# EEM_Connectors.net
KiCad netlist of a schematic drawn in Altium Designer
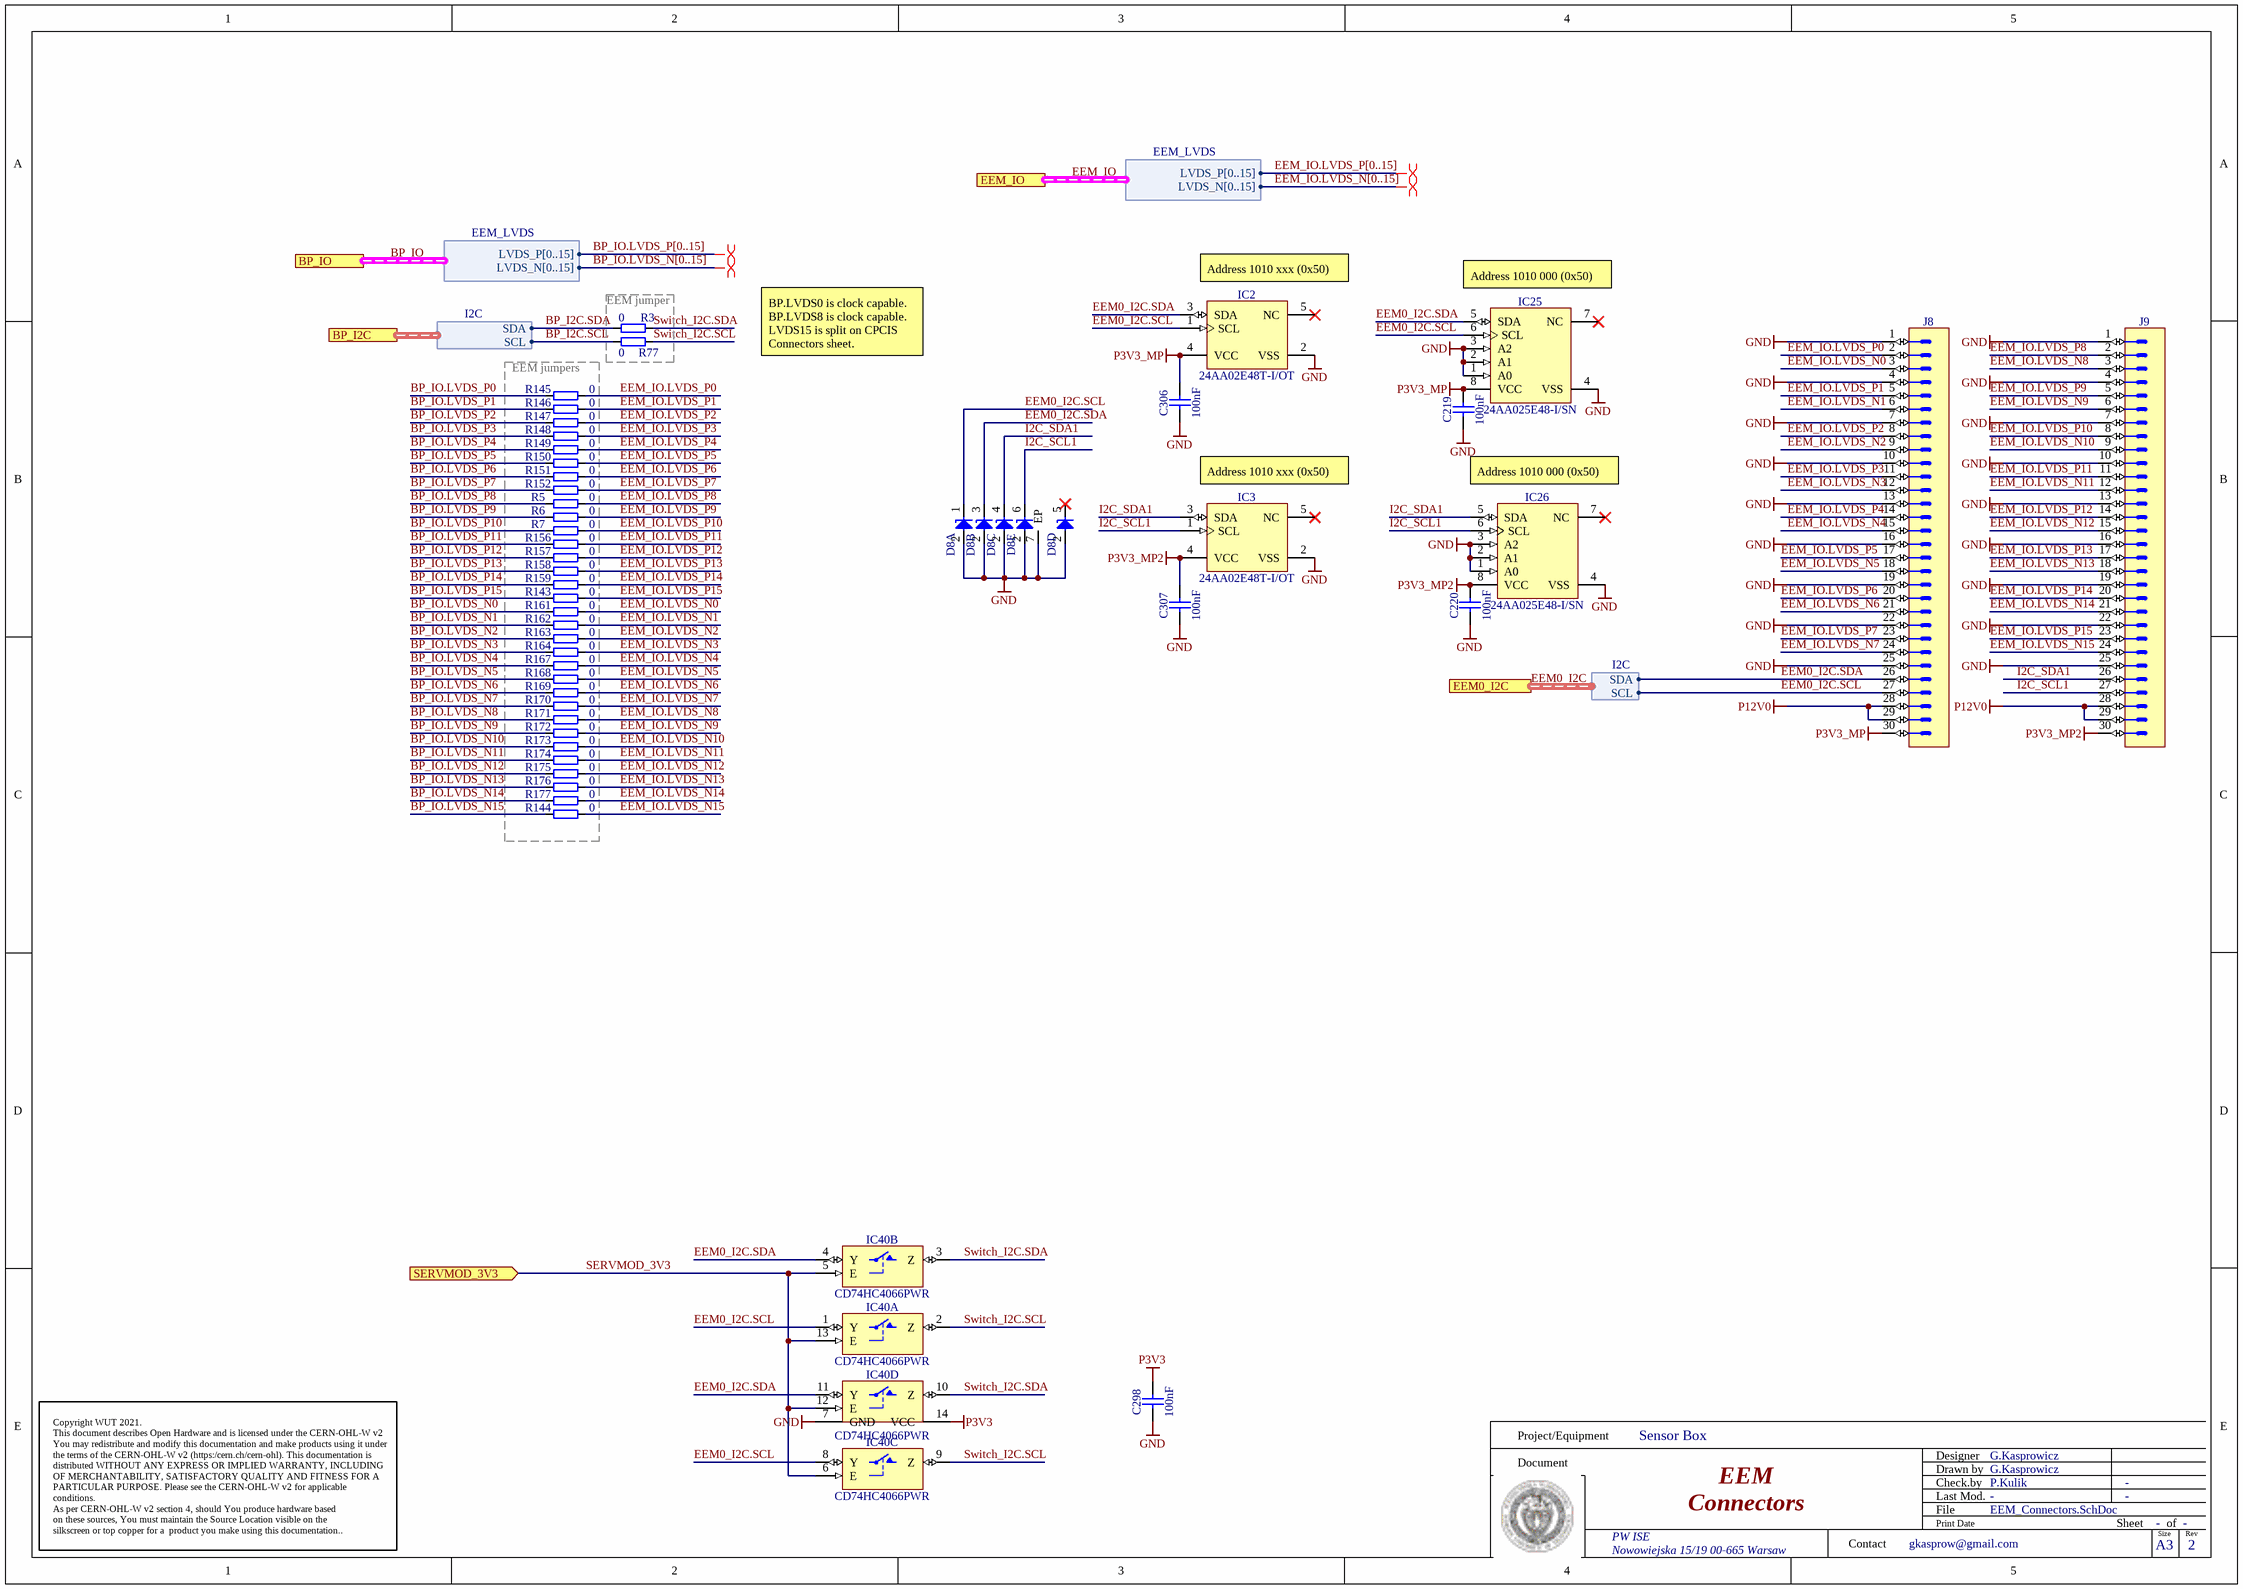
[diagram p0: EEM_Connectors.SchDoc]

(export (version "E")
  (design (tool "Eeschema 10.0.6"))
  (components
    (comp (ref "C219")
      (value "100nF")
      (footprint "CAPC1005X55N")
      (description "Non-polarised capacitor")
      (fields
        (field (name "PART NUMBER") "CC0402_100NF_50V_10%_X7R")
        (field (name "VOLTAGE") "50V")
        (field (name "AUTHOR") "CERN DEM MR")
      )
      (libsource (lib "Capacitors") (part "Capacitor - non polarized"))
    )
    (comp (ref "C220")
      (value "100nF")
      (footprint "CAPC1005X55N")
      (description "Non-polarised capacitor")
      (fields
        (field (name "PART NUMBER") "CC0402_100NF_50V_10%_X7R")
        (field (name "VOLTAGE") "50V")
        (field (name "AUTHOR") "CERN DEM MR")
      )
      (libsource (lib "Capacitors") (part "Capacitor - non polarized"))
    )
    (comp (ref "C298")
      (value "100nF")
      (footprint "CAPC1005X55N")
      (description "Non-polarised capacitor")
      (fields
        (field (name "PART NUMBER") "CC0402_100NF_50V_10%_X7R")
        (field (name "VOLTAGE") "50V")
        (field (name "AUTHOR") "CERN DEM MR")
      )
      (libsource (lib "Capacitors") (part "Capacitor - non polarized"))
    )
    (comp (ref "C306")
      (value "100nF")
      (footprint "CAPC1005X55N")
      (description "Non-polarised capacitor")
      (fields
        (field (name "PART NUMBER") "CC0402_100NF_50V_10%_X7R")
        (field (name "VOLTAGE") "50V")
        (field (name "AUTHOR") "CERN DEM MR")
      )
      (libsource (lib "Capacitors") (part "Capacitor - non polarized"))
    )
    (comp (ref "C307")
      (value "100nF")
      (footprint "CAPC1005X55N")
      (description "Non-polarised capacitor")
      (fields
        (field (name "PART NUMBER") "CC0402_100NF_50V_10%_X7R")
        (field (name "VOLTAGE") "50V")
        (field (name "AUTHOR") "CERN DEM MR")
      )
      (libsource (lib "Capacitors") (part "Capacitor - non polarized"))
    )
    (comp (ref "D8")
      (value "UCLAMP3305P.TCT")
      (footprint "SON50P160X65_HS-7N")
      (description "Diode TVS Quint Common Anode Uni-Dir 3.3V 40W 6-Pin SLP EP T/R")
      (libsource (lib "TechnoSystem Workspace") (part "D-AK-2"))
    )
    (comp (ref "IC2")
      (value "24AA02E48T-I/OT")
      (footprint "SOT95P280X145-5N")
      (description "1.7V-5.5V, 2K I2C Serial EEPROM With EUI-48 Node Identity")
      (fields (field (name "MANUFACTURER") "MICROCHIP TECHNOLOGY") (field (name "AUTHOR") "CERN DEM MR"))
      (libsource (lib "ICs And Semiconductors") (part "24AA02E48T-I/OT"))
    )
    (comp (ref "IC3")
      (value "24AA02E48T-I/OT")
      (footprint "SOT95P280X145-5N")
      (description "1.7V-5.5V, 2K I2C Serial EEPROM With EUI-48 Node Identity")
      (fields (field (name "MANUFACTURER") "MICROCHIP TECHNOLOGY") (field (name "AUTHOR") "CERN DEM MR"))
      (libsource (lib "ICs And Semiconductors") (part "24AA02E48T-I/OT"))
    )
    (comp (ref "IC25")
      (value "24AA025E48-I/SN")
      (footprint "SOIC127P600X175-8N")
      (description "1.7V-5.5V, 2K I2C™ Serial EEPROMs with EUI-48™ Node Identity")
      (fields (field (name "MANUFACTURER") "MICROCHIP TECHNOLOGY") (field (name "AUTHOR") "CERN DEM MR"))
      (libsource (lib "ICs And Semiconductors") (part "24AA025E48-I/SN"))
    )
    (comp (ref "IC26")
      (value "24AA025E48-I/SN")
      (footprint "SOIC127P600X175-8N")
      (description "1.7V-5.5V, 2K I2C™ Serial EEPROMs with EUI-48™ Node Identity")
      (fields (field (name "MANUFACTURER") "MICROCHIP TECHNOLOGY") (field (name "AUTHOR") "CERN DEM MR"))
      (libsource (lib "ICs And Semiconductors") (part "24AA025E48-I/SN"))
    )
    (comp (ref "IC40")
      (value "CD74HC4066PWR")
      (footprint "CD74HC4066PWR")
      (description "12-V, 1: 1 (SPST), (SPST), 4-channel analog switch 14-TSSOP -55 to 125")
      (libsource (lib "TechnoSystem Workspace") (part "CD74HC4066PWR-Symbol-1"))
    )
    (comp (ref "J8")
      (value "~")
      (footprint "3M_N2530-6002RB")
      (description "Connector 30 Male")
      (fields
        (field (name "PART NUMBER") "3M_N2530-6002RB")
        (field (name "MANUFACTURER") "3M")
        (field (name "AUTHOR") "CERN DEM JLC")
      )
      (libsource (lib "Connectors") (part "Connector 30 Male"))
    )
    (comp (ref "J9")
      (value "~")
      (footprint "3M_N2530-6002RB")
      (description "Connector 30 Male")
      (fields
        (field (name "PART NUMBER") "3M_N2530-6002RB")
        (field (name "MANUFACTURER") "3M")
        (field (name "AUTHOR") "CERN DEM JLC")
      )
      (libsource (lib "Connectors") (part "Connector 30 Male"))
    )
    (comp (ref "R3")
      (value "0")
      (footprint "RESC1005X40N")
      (description "Resistor")
      (fields
        (field (name "PART NUMBER") "R0402_0R_JUMPER")
        (field (name "MANUFACTURER") "GENERIC")
        (field (name "AUTHOR") "CERN DEM JLC")
      )
      (libsource (lib "Resistors") (part "Resistor"))
    )
    (comp (ref "R5")
      (value "0")
      (footprint "RESC1005X40N")
      (description "Resistor")
      (fields
        (field (name "PART NUMBER") "R0402_0R_JUMPER")
        (field (name "MANUFACTURER") "GENERIC")
        (field (name "AUTHOR") "CERN DEM JLC")
      )
      (libsource (lib "Resistors") (part "Resistor"))
    )
    (comp (ref "R6")
      (value "0")
      (footprint "RESC1005X40N")
      (description "Resistor")
      (fields
        (field (name "PART NUMBER") "R0402_0R_JUMPER")
        (field (name "MANUFACTURER") "GENERIC")
        (field (name "AUTHOR") "CERN DEM JLC")
      )
      (libsource (lib "Resistors") (part "Resistor"))
    )
    (comp (ref "R7")
      (value "0")
      (footprint "RESC1005X40N")
      (description "Resistor")
      (fields
        (field (name "PART NUMBER") "R0402_0R_JUMPER")
        (field (name "MANUFACTURER") "GENERIC")
        (field (name "AUTHOR") "CERN DEM JLC")
      )
      (libsource (lib "Resistors") (part "Resistor"))
    )
    (comp (ref "R77")
      (value "0")
      (footprint "RESC1005X40N")
      (description "Resistor")
      (fields
        (field (name "PART NUMBER") "R0402_0R_JUMPER")
        (field (name "MANUFACTURER") "GENERIC")
        (field (name "AUTHOR") "CERN DEM JLC")
      )
      (libsource (lib "Resistors") (part "Resistor"))
    )
    (comp (ref "R143")
      (value "0")
      (footprint "RESC1005X40N")
      (description "Resistor")
      (fields
        (field (name "PART NUMBER") "R0402_0R_JUMPER")
        (field (name "MANUFACTURER") "GENERIC")
        (field (name "AUTHOR") "CERN DEM JLC")
      )
      (libsource (lib "Resistors") (part "Resistor"))
    )
    (comp (ref "R144")
      (value "0")
      (footprint "RESC1005X40N")
      (description "Resistor")
      (fields
        (field (name "PART NUMBER") "R0402_0R_JUMPER")
        (field (name "MANUFACTURER") "GENERIC")
        (field (name "AUTHOR") "CERN DEM JLC")
      )
      (libsource (lib "Resistors") (part "Resistor"))
    )
    (comp (ref "R145")
      (value "0")
      (footprint "RESC1005X40N")
      (description "Resistor")
      (fields
        (field (name "PART NUMBER") "R0402_0R_JUMPER")
        (field (name "MANUFACTURER") "GENERIC")
        (field (name "AUTHOR") "CERN DEM JLC")
      )
      (libsource (lib "Resistors") (part "Resistor"))
    )
    (comp (ref "R146")
      (value "0")
      (footprint "RESC1005X40N")
      (description "Resistor")
      (fields
        (field (name "PART NUMBER") "R0402_0R_JUMPER")
        (field (name "MANUFACTURER") "GENERIC")
        (field (name "AUTHOR") "CERN DEM JLC")
      )
      (libsource (lib "Resistors") (part "Resistor"))
    )
    (comp (ref "R147")
      (value "0")
      (footprint "RESC1005X40N")
      (description "Resistor")
      (fields
        (field (name "PART NUMBER") "R0402_0R_JUMPER")
        (field (name "MANUFACTURER") "GENERIC")
        (field (name "AUTHOR") "CERN DEM JLC")
      )
      (libsource (lib "Resistors") (part "Resistor"))
    )
    (comp (ref "R148")
      (value "0")
      (footprint "RESC1005X40N")
      (description "Resistor")
      (fields
        (field (name "PART NUMBER") "R0402_0R_JUMPER")
        (field (name "MANUFACTURER") "GENERIC")
        (field (name "AUTHOR") "CERN DEM JLC")
      )
      (libsource (lib "Resistors") (part "Resistor"))
    )
    (comp (ref "R149")
      (value "0")
      (footprint "RESC1005X40N")
      (description "Resistor")
      (fields
        (field (name "PART NUMBER") "R0402_0R_JUMPER")
        (field (name "MANUFACTURER") "GENERIC")
        (field (name "AUTHOR") "CERN DEM JLC")
      )
      (libsource (lib "Resistors") (part "Resistor"))
    )
    (comp (ref "R150")
      (value "0")
      (footprint "RESC1005X40N")
      (description "Resistor")
      (fields
        (field (name "PART NUMBER") "R0402_0R_JUMPER")
        (field (name "MANUFACTURER") "GENERIC")
        (field (name "AUTHOR") "CERN DEM JLC")
      )
      (libsource (lib "Resistors") (part "Resistor"))
    )
    (comp (ref "R151")
      (value "0")
      (footprint "RESC1005X40N")
      (description "Resistor")
      (fields
        (field (name "PART NUMBER") "R0402_0R_JUMPER")
        (field (name "MANUFACTURER") "GENERIC")
        (field (name "AUTHOR") "CERN DEM JLC")
      )
      (libsource (lib "Resistors") (part "Resistor"))
    )
    (comp (ref "R152")
      (value "0")
      (footprint "RESC1005X40N")
      (description "Resistor")
      (fields
        (field (name "PART NUMBER") "R0402_0R_JUMPER")
        (field (name "MANUFACTURER") "GENERIC")
        (field (name "AUTHOR") "CERN DEM JLC")
      )
      (libsource (lib "Resistors") (part "Resistor"))
    )
    (comp (ref "R156")
      (value "0")
      (footprint "RESC1005X40N")
      (description "Resistor")
      (fields
        (field (name "PART NUMBER") "R0402_0R_JUMPER")
        (field (name "MANUFACTURER") "GENERIC")
        (field (name "AUTHOR") "CERN DEM JLC")
      )
      (libsource (lib "Resistors") (part "Resistor"))
    )
    (comp (ref "R157")
      (value "0")
      (footprint "RESC1005X40N")
      (description "Resistor")
      (fields
        (field (name "PART NUMBER") "R0402_0R_JUMPER")
        (field (name "MANUFACTURER") "GENERIC")
        (field (name "AUTHOR") "CERN DEM JLC")
      )
      (libsource (lib "Resistors") (part "Resistor"))
    )
    (comp (ref "R158")
      (value "0")
      (footprint "RESC1005X40N")
      (description "Resistor")
      (fields
        (field (name "PART NUMBER") "R0402_0R_JUMPER")
        (field (name "MANUFACTURER") "GENERIC")
        (field (name "AUTHOR") "CERN DEM JLC")
      )
      (libsource (lib "Resistors") (part "Resistor"))
    )
    (comp (ref "R159")
      (value "0")
      (footprint "RESC1005X40N")
      (description "Resistor")
      (fields
        (field (name "PART NUMBER") "R0402_0R_JUMPER")
        (field (name "MANUFACTURER") "GENERIC")
        (field (name "AUTHOR") "CERN DEM JLC")
      )
      (libsource (lib "Resistors") (part "Resistor"))
    )
    (comp (ref "R161")
      (value "0")
      (footprint "RESC1005X40N")
      (description "Resistor")
      (fields
        (field (name "PART NUMBER") "R0402_0R_JUMPER")
        (field (name "MANUFACTURER") "GENERIC")
        (field (name "AUTHOR") "CERN DEM JLC")
      )
      (libsource (lib "Resistors") (part "Resistor"))
    )
    (comp (ref "R162")
      (value "0")
      (footprint "RESC1005X40N")
      (description "Resistor")
      (fields
        (field (name "PART NUMBER") "R0402_0R_JUMPER")
        (field (name "MANUFACTURER") "GENERIC")
        (field (name "AUTHOR") "CERN DEM JLC")
      )
      (libsource (lib "Resistors") (part "Resistor"))
    )
    (comp (ref "R163")
      (value "0")
      (footprint "RESC1005X40N")
      (description "Resistor")
      (fields
        (field (name "PART NUMBER") "R0402_0R_JUMPER")
        (field (name "MANUFACTURER") "GENERIC")
        (field (name "AUTHOR") "CERN DEM JLC")
      )
      (libsource (lib "Resistors") (part "Resistor"))
    )
    (comp (ref "R164")
      (value "0")
      (footprint "RESC1005X40N")
      (description "Resistor")
      (fields
        (field (name "PART NUMBER") "R0402_0R_JUMPER")
        (field (name "MANUFACTURER") "GENERIC")
        (field (name "AUTHOR") "CERN DEM JLC")
      )
      (libsource (lib "Resistors") (part "Resistor"))
    )
    (comp (ref "R167")
      (value "0")
      (footprint "RESC1005X40N")
      (description "Resistor")
      (fields
        (field (name "PART NUMBER") "R0402_0R_JUMPER")
        (field (name "MANUFACTURER") "GENERIC")
        (field (name "AUTHOR") "CERN DEM JLC")
      )
      (libsource (lib "Resistors") (part "Resistor"))
    )
    (comp (ref "R168")
      (value "0")
      (footprint "RESC1005X40N")
      (description "Resistor")
      (fields
        (field (name "PART NUMBER") "R0402_0R_JUMPER")
        (field (name "MANUFACTURER") "GENERIC")
        (field (name "AUTHOR") "CERN DEM JLC")
      )
      (libsource (lib "Resistors") (part "Resistor"))
    )
    (comp (ref "R169")
      (value "0")
      (footprint "RESC1005X40N")
      (description "Resistor")
      (fields
        (field (name "PART NUMBER") "R0402_0R_JUMPER")
        (field (name "MANUFACTURER") "GENERIC")
        (field (name "AUTHOR") "CERN DEM JLC")
      )
      (libsource (lib "Resistors") (part "Resistor"))
    )
    (comp (ref "R170")
      (value "0")
      (footprint "RESC1005X40N")
      (description "Resistor")
      (fields
        (field (name "PART NUMBER") "R0402_0R_JUMPER")
        (field (name "MANUFACTURER") "GENERIC")
        (field (name "AUTHOR") "CERN DEM JLC")
      )
      (libsource (lib "Resistors") (part "Resistor"))
    )
    (comp (ref "R171")
      (value "0")
      (footprint "RESC1005X40N")
      (description "Resistor")
      (fields
        (field (name "PART NUMBER") "R0402_0R_JUMPER")
        (field (name "MANUFACTURER") "GENERIC")
        (field (name "AUTHOR") "CERN DEM JLC")
      )
      (libsource (lib "Resistors") (part "Resistor"))
    )
    (comp (ref "R172")
      (value "0")
      (footprint "RESC1005X40N")
      (description "Resistor")
      (fields
        (field (name "PART NUMBER") "R0402_0R_JUMPER")
        (field (name "MANUFACTURER") "GENERIC")
        (field (name "AUTHOR") "CERN DEM JLC")
      )
      (libsource (lib "Resistors") (part "Resistor"))
    )
    (comp (ref "R173")
      (value "0")
      (footprint "RESC1005X40N")
      (description "Resistor")
      (fields
        (field (name "PART NUMBER") "R0402_0R_JUMPER")
        (field (name "MANUFACTURER") "GENERIC")
        (field (name "AUTHOR") "CERN DEM JLC")
      )
      (libsource (lib "Resistors") (part "Resistor"))
    )
    (comp (ref "R174")
      (value "0")
      (footprint "RESC1005X40N")
      (description "Resistor")
      (fields
        (field (name "PART NUMBER") "R0402_0R_JUMPER")
        (field (name "MANUFACTURER") "GENERIC")
        (field (name "AUTHOR") "CERN DEM JLC")
      )
      (libsource (lib "Resistors") (part "Resistor"))
    )
    (comp (ref "R175")
      (value "0")
      (footprint "RESC1005X40N")
      (description "Resistor")
      (fields
        (field (name "PART NUMBER") "R0402_0R_JUMPER")
        (field (name "MANUFACTURER") "GENERIC")
        (field (name "AUTHOR") "CERN DEM JLC")
      )
      (libsource (lib "Resistors") (part "Resistor"))
    )
    (comp (ref "R176")
      (value "0")
      (footprint "RESC1005X40N")
      (description "Resistor")
      (fields
        (field (name "PART NUMBER") "R0402_0R_JUMPER")
        (field (name "MANUFACTURER") "GENERIC")
        (field (name "AUTHOR") "CERN DEM JLC")
      )
      (libsource (lib "Resistors") (part "Resistor"))
    )
    (comp (ref "R177")
      (value "0")
      (footprint "RESC1005X40N")
      (description "Resistor")
      (fields
        (field (name "PART NUMBER") "R0402_0R_JUMPER")
        (field (name "MANUFACTURER") "GENERIC")
        (field (name "AUTHOR") "CERN DEM JLC")
      )
      (libsource (lib "Resistors") (part "Resistor"))
    )
  )
  (nets
    (net (code "5") (name "/BP_I2C.SCL") (class "Default")
      (node (ref "R77") (pin "1") (pinfunction "1_1") (pintype "passive"))
    )
    (net (code "6") (name "/BP_I2C.SDA") (class "Default")
      (node (ref "R3") (pin "1") (pinfunction "1_1") (pintype "passive"))
    )
    (net (code "7") (name "/BP_IO.LVDS_N0") (class "Default")
      (node (ref "R161") (pin "1") (pinfunction "1_1") (pintype "passive"))
    )
    (net (code "8") (name "/BP_IO.LVDS_N1") (class "Default")
      (node (ref "R162") (pin "1") (pinfunction "1_1") (pintype "passive"))
    )
    (net (code "9") (name "/BP_IO.LVDS_N2") (class "Default")
      (node (ref "R163") (pin "1") (pinfunction "1_1") (pintype "passive"))
    )
    (net (code "10") (name "/BP_IO.LVDS_N3") (class "Default")
      (node (ref "R164") (pin "1") (pinfunction "1_1") (pintype "passive"))
    )
    (net (code "11") (name "/BP_IO.LVDS_N4") (class "Default")
      (node (ref "R167") (pin "1") (pinfunction "1_1") (pintype "passive"))
    )
    (net (code "12") (name "/BP_IO.LVDS_N5") (class "Default")
      (node (ref "R168") (pin "1") (pinfunction "1_1") (pintype "passive"))
    )
    (net (code "13") (name "/BP_IO.LVDS_N6") (class "Default")
      (node (ref "R169") (pin "1") (pinfunction "1_1") (pintype "passive"))
    )
    (net (code "14") (name "/BP_IO.LVDS_N7") (class "Default")
      (node (ref "R170") (pin "1") (pinfunction "1_1") (pintype "passive"))
    )
    (net (code "15") (name "/BP_IO.LVDS_N8") (class "Default")
      (node (ref "R171") (pin "1") (pinfunction "1_1") (pintype "passive"))
    )
    (net (code "16") (name "/BP_IO.LVDS_N9") (class "Default")
      (node (ref "R172") (pin "1") (pinfunction "1_1") (pintype "passive"))
    )
    (net (code "17") (name "/BP_IO.LVDS_N10") (class "Default")
      (node (ref "R173") (pin "1") (pinfunction "1_1") (pintype "passive"))
    )
    (net (code "18") (name "/BP_IO.LVDS_N11") (class "Default")
      (node (ref "R174") (pin "1") (pinfunction "1_1") (pintype "passive"))
    )
    (net (code "19") (name "/BP_IO.LVDS_N12") (class "Default")
      (node (ref "R175") (pin "1") (pinfunction "1_1") (pintype "passive"))
    )
    (net (code "20") (name "/BP_IO.LVDS_N13") (class "Default")
      (node (ref "R176") (pin "1") (pinfunction "1_1") (pintype "passive"))
    )
    (net (code "21") (name "/BP_IO.LVDS_N14") (class "Default")
      (node (ref "R177") (pin "1") (pinfunction "1_1") (pintype "passive"))
    )
    (net (code "22") (name "/BP_IO.LVDS_N15") (class "Default")
      (node (ref "R144") (pin "2") (pinfunction "2_2") (pintype "passive"))
    )
    (net (code "23") (name "/BP_IO.LVDS_P0") (class "Default")
      (node (ref "R145") (pin "1") (pinfunction "1_1") (pintype "passive"))
    )
    (net (code "24") (name "/BP_IO.LVDS_P1") (class "Default")
      (node (ref "R146") (pin "1") (pinfunction "1_1") (pintype "passive"))
    )
    (net (code "25") (name "/BP_IO.LVDS_P2") (class "Default")
      (node (ref "R147") (pin "1") (pinfunction "1_1") (pintype "passive"))
    )
    (net (code "26") (name "/BP_IO.LVDS_P3") (class "Default")
      (node (ref "R148") (pin "1") (pinfunction "1_1") (pintype "passive"))
    )
    (net (code "27") (name "/BP_IO.LVDS_P4") (class "Default")
      (node (ref "R149") (pin "1") (pinfunction "1_1") (pintype "passive"))
    )
    (net (code "28") (name "/BP_IO.LVDS_P5") (class "Default")
      (node (ref "R150") (pin "1") (pinfunction "1_1") (pintype "passive"))
    )
    (net (code "29") (name "/BP_IO.LVDS_P6") (class "Default")
      (node (ref "R151") (pin "1") (pinfunction "1_1") (pintype "passive"))
    )
    (net (code "30") (name "/BP_IO.LVDS_P7") (class "Default")
      (node (ref "R152") (pin "1") (pinfunction "1_1") (pintype "passive"))
    )
    (net (code "31") (name "/BP_IO.LVDS_P8") (class "Default")
      (node (ref "R5") (pin "1") (pinfunction "1_1") (pintype "passive"))
    )
    (net (code "32") (name "/BP_IO.LVDS_P9") (class "Default")
      (node (ref "R6") (pin "1") (pinfunction "1_1") (pintype "passive"))
    )
    (net (code "33") (name "/BP_IO.LVDS_P10") (class "Default")
      (node (ref "R7") (pin "1") (pinfunction "1_1") (pintype "passive"))
    )
    (net (code "34") (name "/BP_IO.LVDS_P11") (class "Default")
      (node (ref "R156") (pin "1") (pinfunction "1_1") (pintype "passive"))
    )
    (net (code "35") (name "/BP_IO.LVDS_P12") (class "Default")
      (node (ref "R157") (pin "1") (pinfunction "1_1") (pintype "passive"))
    )
    (net (code "36") (name "/BP_IO.LVDS_P13") (class "Default")
      (node (ref "R158") (pin "1") (pinfunction "1_1") (pintype "passive"))
    )
    (net (code "37") (name "/BP_IO.LVDS_P14") (class "Default")
      (node (ref "R159") (pin "1") (pinfunction "1_1") (pintype "passive"))
    )
    (net (code "38") (name "/BP_IO.LVDS_P15") (class "Default")
      (node (ref "R143") (pin "2") (pinfunction "2_2") (pintype "passive"))
    )
    (net (code "40") (name "/EEM0_I2C.SCL") (class "Default")
      (node (ref "D8") (pin "1") (pinfunction "C_1") (pintype "passive"))
      (node (ref "IC2") (pin "1") (pinfunction "SCL_1") (pintype "input"))
      (node (ref "IC25") (pin "6") (pinfunction "SCL_6") (pintype "input"))
      (node (ref "IC40") (pin "1") (pinfunction "Y_1") (pintype "bidirectional"))
      (node (ref "IC40") (pin "8") (pinfunction "Y_8") (pintype "bidirectional"))
      (node (ref "J8") (pin "27") (pinfunction "27_27") (pintype "bidirectional"))
    )
    (net (code "41") (name "/EEM0_I2C.SDA") (class "Default")
      (node (ref "D8") (pin "3") (pinfunction "C_3") (pintype "passive"))
      (node (ref "IC2") (pin "3") (pinfunction "SDA_3") (pintype "bidirectional"))
      (node (ref "IC25") (pin "5") (pinfunction "SDA_5") (pintype "bidirectional"))
      (node (ref "IC40") (pin "11") (pinfunction "Y_11") (pintype "bidirectional"))
      (node (ref "IC40") (pin "4") (pinfunction "Y_4") (pintype "bidirectional"))
      (node (ref "J8") (pin "26") (pinfunction "26_26") (pintype "bidirectional"))
    )
    (net (code "43") (name "/EEM_IO.LVDS_N0") (class "Default")
      (node (ref "J8") (pin "3") (pinfunction "3_3") (pintype "bidirectional"))
      (node (ref "R161") (pin "2") (pinfunction "2_2") (pintype "passive"))
    )
    (net (code "44") (name "/EEM_IO.LVDS_N1") (class "Default")
      (node (ref "J8") (pin "6") (pinfunction "6_6") (pintype "bidirectional"))
      (node (ref "R162") (pin "2") (pinfunction "2_2") (pintype "passive"))
    )
    (net (code "45") (name "/EEM_IO.LVDS_N2") (class "Default")
      (node (ref "J8") (pin "9") (pinfunction "9_9") (pintype "bidirectional"))
      (node (ref "R163") (pin "2") (pinfunction "2_2") (pintype "passive"))
    )
    (net (code "46") (name "/EEM_IO.LVDS_N3") (class "Default")
      (node (ref "J8") (pin "12") (pinfunction "12_12") (pintype "bidirectional"))
      (node (ref "R164") (pin "2") (pinfunction "2_2") (pintype "passive"))
    )
    (net (code "47") (name "/EEM_IO.LVDS_N4") (class "Default")
      (node (ref "J8") (pin "15") (pinfunction "15_15") (pintype "bidirectional"))
      (node (ref "R167") (pin "2") (pinfunction "2_2") (pintype "passive"))
    )
    (net (code "48") (name "/EEM_IO.LVDS_N5") (class "Default")
      (node (ref "J8") (pin "18") (pinfunction "18_18") (pintype "bidirectional"))
      (node (ref "R168") (pin "2") (pinfunction "2_2") (pintype "passive"))
    )
    (net (code "49") (name "/EEM_IO.LVDS_N6") (class "Default")
      (node (ref "J8") (pin "21") (pinfunction "21_21") (pintype "bidirectional"))
      (node (ref "R169") (pin "2") (pinfunction "2_2") (pintype "passive"))
    )
    (net (code "50") (name "/EEM_IO.LVDS_N7") (class "Default")
      (node (ref "J8") (pin "24") (pinfunction "24_24") (pintype "bidirectional"))
      (node (ref "R170") (pin "2") (pinfunction "2_2") (pintype "passive"))
    )
    (net (code "51") (name "/EEM_IO.LVDS_N8") (class "Default")
      (node (ref "J9") (pin "3") (pinfunction "3_3") (pintype "bidirectional"))
      (node (ref "R171") (pin "2") (pinfunction "2_2") (pintype "passive"))
    )
    (net (code "52") (name "/EEM_IO.LVDS_N9") (class "Default")
      (node (ref "J9") (pin "6") (pinfunction "6_6") (pintype "bidirectional"))
      (node (ref "R172") (pin "2") (pinfunction "2_2") (pintype "passive"))
    )
    (net (code "53") (name "/EEM_IO.LVDS_N10") (class "Default")
      (node (ref "J9") (pin "9") (pinfunction "9_9") (pintype "bidirectional"))
      (node (ref "R173") (pin "2") (pinfunction "2_2") (pintype "passive"))
    )
    (net (code "54") (name "/EEM_IO.LVDS_N11") (class "Default")
      (node (ref "J9") (pin "12") (pinfunction "12_12") (pintype "bidirectional"))
      (node (ref "R174") (pin "2") (pinfunction "2_2") (pintype "passive"))
    )
    (net (code "55") (name "/EEM_IO.LVDS_N12") (class "Default")
      (node (ref "J9") (pin "15") (pinfunction "15_15") (pintype "bidirectional"))
      (node (ref "R175") (pin "2") (pinfunction "2_2") (pintype "passive"))
    )
    (net (code "56") (name "/EEM_IO.LVDS_N13") (class "Default")
      (node (ref "J9") (pin "18") (pinfunction "18_18") (pintype "bidirectional"))
      (node (ref "R176") (pin "2") (pinfunction "2_2") (pintype "passive"))
    )
    (net (code "57") (name "/EEM_IO.LVDS_N14") (class "Default")
      (node (ref "J9") (pin "21") (pinfunction "21_21") (pintype "bidirectional"))
      (node (ref "R177") (pin "2") (pinfunction "2_2") (pintype "passive"))
    )
    (net (code "58") (name "/EEM_IO.LVDS_N15") (class "Default")
      (node (ref "J9") (pin "24") (pinfunction "24_24") (pintype "bidirectional"))
      (node (ref "R144") (pin "1") (pinfunction "1_1") (pintype "passive"))
    )
    (net (code "60") (name "/EEM_IO.LVDS_P0") (class "Default")
      (node (ref "J8") (pin "2") (pinfunction "2_2") (pintype "bidirectional"))
      (node (ref "R145") (pin "2") (pinfunction "2_2") (pintype "passive"))
    )
    (net (code "61") (name "/EEM_IO.LVDS_P1") (class "Default")
      (node (ref "J8") (pin "5") (pinfunction "5_5") (pintype "bidirectional"))
      (node (ref "R146") (pin "2") (pinfunction "2_2") (pintype "passive"))
    )
    (net (code "62") (name "/EEM_IO.LVDS_P2") (class "Default")
      (node (ref "J8") (pin "8") (pinfunction "8_8") (pintype "bidirectional"))
      (node (ref "R147") (pin "2") (pinfunction "2_2") (pintype "passive"))
    )
    (net (code "63") (name "/EEM_IO.LVDS_P3") (class "Default")
      (node (ref "J8") (pin "11") (pinfunction "11_11") (pintype "bidirectional"))
      (node (ref "R148") (pin "2") (pinfunction "2_2") (pintype "passive"))
    )
    (net (code "64") (name "/EEM_IO.LVDS_P4") (class "Default")
      (node (ref "J8") (pin "14") (pinfunction "14_14") (pintype "bidirectional"))
      (node (ref "R149") (pin "2") (pinfunction "2_2") (pintype "passive"))
    )
    (net (code "65") (name "/EEM_IO.LVDS_P5") (class "Default")
      (node (ref "J8") (pin "17") (pinfunction "17_17") (pintype "bidirectional"))
      (node (ref "R150") (pin "2") (pinfunction "2_2") (pintype "passive"))
    )
    (net (code "66") (name "/EEM_IO.LVDS_P6") (class "Default")
      (node (ref "J8") (pin "20") (pinfunction "20_20") (pintype "bidirectional"))
      (node (ref "R151") (pin "2") (pinfunction "2_2") (pintype "passive"))
    )
    (net (code "67") (name "/EEM_IO.LVDS_P7") (class "Default")
      (node (ref "J8") (pin "23") (pinfunction "23_23") (pintype "bidirectional"))
      (node (ref "R152") (pin "2") (pinfunction "2_2") (pintype "passive"))
    )
    (net (code "68") (name "/EEM_IO.LVDS_P8") (class "Default")
      (node (ref "J9") (pin "2") (pinfunction "2_2") (pintype "bidirectional"))
      (node (ref "R5") (pin "2") (pinfunction "2_2") (pintype "passive"))
    )
    (net (code "69") (name "/EEM_IO.LVDS_P9") (class "Default")
      (node (ref "J9") (pin "5") (pinfunction "5_5") (pintype "bidirectional"))
      (node (ref "R6") (pin "2") (pinfunction "2_2") (pintype "passive"))
    )
    (net (code "70") (name "/EEM_IO.LVDS_P10") (class "Default")
      (node (ref "J9") (pin "8") (pinfunction "8_8") (pintype "bidirectional"))
      (node (ref "R7") (pin "2") (pinfunction "2_2") (pintype "passive"))
    )
    (net (code "71") (name "/EEM_IO.LVDS_P11") (class "Default")
      (node (ref "J9") (pin "11") (pinfunction "11_11") (pintype "bidirectional"))
      (node (ref "R156") (pin "2") (pinfunction "2_2") (pintype "passive"))
    )
    (net (code "72") (name "/EEM_IO.LVDS_P12") (class "Default")
      (node (ref "J9") (pin "14") (pinfunction "14_14") (pintype "bidirectional"))
      (node (ref "R157") (pin "2") (pinfunction "2_2") (pintype "passive"))
    )
    (net (code "73") (name "/EEM_IO.LVDS_P13") (class "Default")
      (node (ref "J9") (pin "17") (pinfunction "17_17") (pintype "bidirectional"))
      (node (ref "R158") (pin "2") (pinfunction "2_2") (pintype "passive"))
    )
    (net (code "74") (name "/EEM_IO.LVDS_P14") (class "Default")
      (node (ref "J9") (pin "20") (pinfunction "20_20") (pintype "bidirectional"))
      (node (ref "R159") (pin "2") (pinfunction "2_2") (pintype "passive"))
    )
    (net (code "75") (name "/EEM_IO.LVDS_P15") (class "Default")
      (node (ref "J9") (pin "23") (pinfunction "23_23") (pintype "bidirectional"))
      (node (ref "R143") (pin "1") (pinfunction "1_1") (pintype "passive"))
    )
    (net (code "76") (name "/I2C_SCL1") (class "Default")
      (node (ref "D8") (pin "6") (pinfunction "C_6") (pintype "passive"))
      (node (ref "IC26") (pin "6") (pinfunction "SCL_6") (pintype "input"))
      (node (ref "IC3") (pin "1") (pinfunction "SCL_1") (pintype "input"))
      (node (ref "J9") (pin "27") (pinfunction "27_27") (pintype "bidirectional"))
    )
    (net (code "77") (name "/I2C_SDA1") (class "Default")
      (node (ref "D8") (pin "4") (pinfunction "C_4") (pintype "passive"))
      (node (ref "IC26") (pin "5") (pinfunction "SDA_5") (pintype "bidirectional"))
      (node (ref "IC3") (pin "3") (pinfunction "SDA_3") (pintype "bidirectional"))
      (node (ref "J9") (pin "26") (pinfunction "26_26") (pintype "bidirectional"))
    )
    (net (code "78") (name "/SERVMOD_3V3") (class "Default")
      (node (ref "IC40") (pin "12") (pinfunction "E_12") (pintype "input"))
      (node (ref "IC40") (pin "13") (pinfunction "E_13") (pintype "input"))
      (node (ref "IC40") (pin "5") (pinfunction "E_5") (pintype "input"))
      (node (ref "IC40") (pin "6") (pinfunction "E_6") (pintype "input"))
    )
    (net (code "79") (name "/Switch_I2C.SCL") (class "Default")
      (node (ref "IC40") (pin "2") (pinfunction "Z_2") (pintype "bidirectional"))
      (node (ref "IC40") (pin "9") (pinfunction "Z_9") (pintype "bidirectional"))
      (node (ref "R77") (pin "2") (pinfunction "2_2") (pintype "passive"))
    )
    (net (code "80") (name "/Switch_I2C.SDA") (class "Default")
      (node (ref "IC40") (pin "10") (pinfunction "Z_10") (pintype "bidirectional"))
      (node (ref "IC40") (pin "3") (pinfunction "Z_3") (pintype "bidirectional"))
      (node (ref "R3") (pin "2") (pinfunction "2_2") (pintype "passive"))
    )
    (net (code "85") (name "GND") (class "Default")
      (node (ref "C219") (pin "1") (pinfunction "1_1") (pintype "passive"))
      (node (ref "C220") (pin "1") (pinfunction "1_1") (pintype "passive"))
      (node (ref "C298") (pin "1") (pinfunction "1_1") (pintype "passive"))
      (node (ref "C306") (pin "1") (pinfunction "1_1") (pintype "passive"))
      (node (ref "C307") (pin "1") (pinfunction "1_1") (pintype "passive"))
      (node (ref "D8") (pin "2") (pinfunction "A_2") (pintype "passive"))
      (node (ref "D8") (pin "7") (pinfunction "EP_7") (pintype "passive"))
      (node (ref "IC2") (pin "2") (pinfunction "VSS_2") (pintype "power_in"))
      (node (ref "IC25") (pin "1") (pinfunction "A0_1") (pintype "input"))
      (node (ref "IC25") (pin "2") (pinfunction "A1_2") (pintype "input"))
      (node (ref "IC25") (pin "3") (pinfunction "A2_3") (pintype "input"))
      (node (ref "IC25") (pin "4") (pinfunction "VSS_4") (pintype "power_in"))
      (node (ref "IC26") (pin "1") (pinfunction "A0_1") (pintype "input"))
      (node (ref "IC26") (pin "2") (pinfunction "A1_2") (pintype "input"))
      (node (ref "IC26") (pin "3") (pinfunction "A2_3") (pintype "input"))
      (node (ref "IC26") (pin "4") (pinfunction "VSS_4") (pintype "power_in"))
      (node (ref "IC3") (pin "2") (pinfunction "VSS_2") (pintype "power_in"))
      (node (ref "IC40") (pin "7") (pinfunction "GND_7") (pintype "power_in"))
      (node (ref "J8") (pin "1") (pinfunction "1_1") (pintype "bidirectional"))
      (node (ref "J8") (pin "10") (pinfunction "10_10") (pintype "bidirectional"))
      (node (ref "J8") (pin "13") (pinfunction "13_13") (pintype "bidirectional"))
      (node (ref "J8") (pin "16") (pinfunction "16_16") (pintype "bidirectional"))
      (node (ref "J8") (pin "19") (pinfunction "19_19") (pintype "bidirectional"))
      (node (ref "J8") (pin "22") (pinfunction "22_22") (pintype "bidirectional"))
      (node (ref "J8") (pin "25") (pinfunction "25_25") (pintype "bidirectional"))
      (node (ref "J8") (pin "4") (pinfunction "4_4") (pintype "bidirectional"))
      (node (ref "J8") (pin "7") (pinfunction "7_7") (pintype "bidirectional"))
      (node (ref "J9") (pin "1") (pinfunction "1_1") (pintype "bidirectional"))
      (node (ref "J9") (pin "10") (pinfunction "10_10") (pintype "bidirectional"))
      (node (ref "J9") (pin "13") (pinfunction "13_13") (pintype "bidirectional"))
      (node (ref "J9") (pin "16") (pinfunction "16_16") (pintype "bidirectional"))
      (node (ref "J9") (pin "19") (pinfunction "19_19") (pintype "bidirectional"))
      (node (ref "J9") (pin "22") (pinfunction "22_22") (pintype "bidirectional"))
      (node (ref "J9") (pin "25") (pinfunction "25_25") (pintype "bidirectional"))
      (node (ref "J9") (pin "4") (pinfunction "4_4") (pintype "bidirectional"))
      (node (ref "J9") (pin "7") (pinfunction "7_7") (pintype "bidirectional"))
    )
    (net (code "86") (name "P3V3") (class "Default")
      (node (ref "C298") (pin "2") (pinfunction "2_2") (pintype "passive"))
      (node (ref "IC40") (pin "14") (pinfunction "VCC_14") (pintype "power_in"))
    )
    (net (code "87") (name "P3V3_MP") (class "Default")
      (node (ref "C219") (pin "2") (pinfunction "2_2") (pintype "passive"))
      (node (ref "C306") (pin "2") (pinfunction "2_2") (pintype "passive"))
      (node (ref "IC2") (pin "4") (pinfunction "VCC_4") (pintype "power_in"))
      (node (ref "IC25") (pin "8") (pinfunction "VCC_8") (pintype "power_in"))
      (node (ref "J8") (pin "30") (pinfunction "30_30") (pintype "bidirectional"))
    )
    (net (code "88") (name "P3V3_MP2") (class "Default")
      (node (ref "C220") (pin "2") (pinfunction "2_2") (pintype "passive"))
      (node (ref "C307") (pin "2") (pinfunction "2_2") (pintype "passive"))
      (node (ref "IC26") (pin "8") (pinfunction "VCC_8") (pintype "power_in"))
      (node (ref "IC3") (pin "4") (pinfunction "VCC_4") (pintype "power_in"))
      (node (ref "J9") (pin "30") (pinfunction "30_30") (pintype "bidirectional"))
    )
    (net (code "89") (name "P12V0") (class "Default")
      (node (ref "J8") (pin "28") (pinfunction "28_28") (pintype "bidirectional"))
      (node (ref "J8") (pin "29") (pinfunction "29_29") (pintype "bidirectional"))
      (node (ref "J9") (pin "28") (pinfunction "28_28") (pintype "bidirectional"))
      (node (ref "J9") (pin "29") (pinfunction "29_29") (pintype "bidirectional"))
    )
    (net (code "90") (name "unconnected-(D8D-C-Pad5)") (class "Default")
      (node (ref "D8") (pin "5") (pinfunction "C_5") (pintype "passive+no_connect"))
    )
    (net (code "91") (name "unconnected-(IC2-NC-Pad5)") (class "Default")
      (node (ref "IC2") (pin "5") (pinfunction "NC_5") (pintype "passive+no_connect"))
    )
    (net (code "92") (name "unconnected-(IC3-NC-Pad5)") (class "Default")
      (node (ref "IC3") (pin "5") (pinfunction "NC_5") (pintype "passive+no_connect"))
    )
    (net (code "93") (name "unconnected-(IC25-NC-Pad7)") (class "Default")
      (node (ref "IC25") (pin "7") (pinfunction "NC_7") (pintype "passive+no_connect"))
    )
    (net (code "94") (name "unconnected-(IC26-NC-Pad7)") (class "Default")
      (node (ref "IC26") (pin "7") (pinfunction "NC_7") (pintype "passive+no_connect"))
    )
  )
)
